# ProPrj__B__2024-11-30.net
KiCad netlist of a schematic drawn in EasyEDA Pro
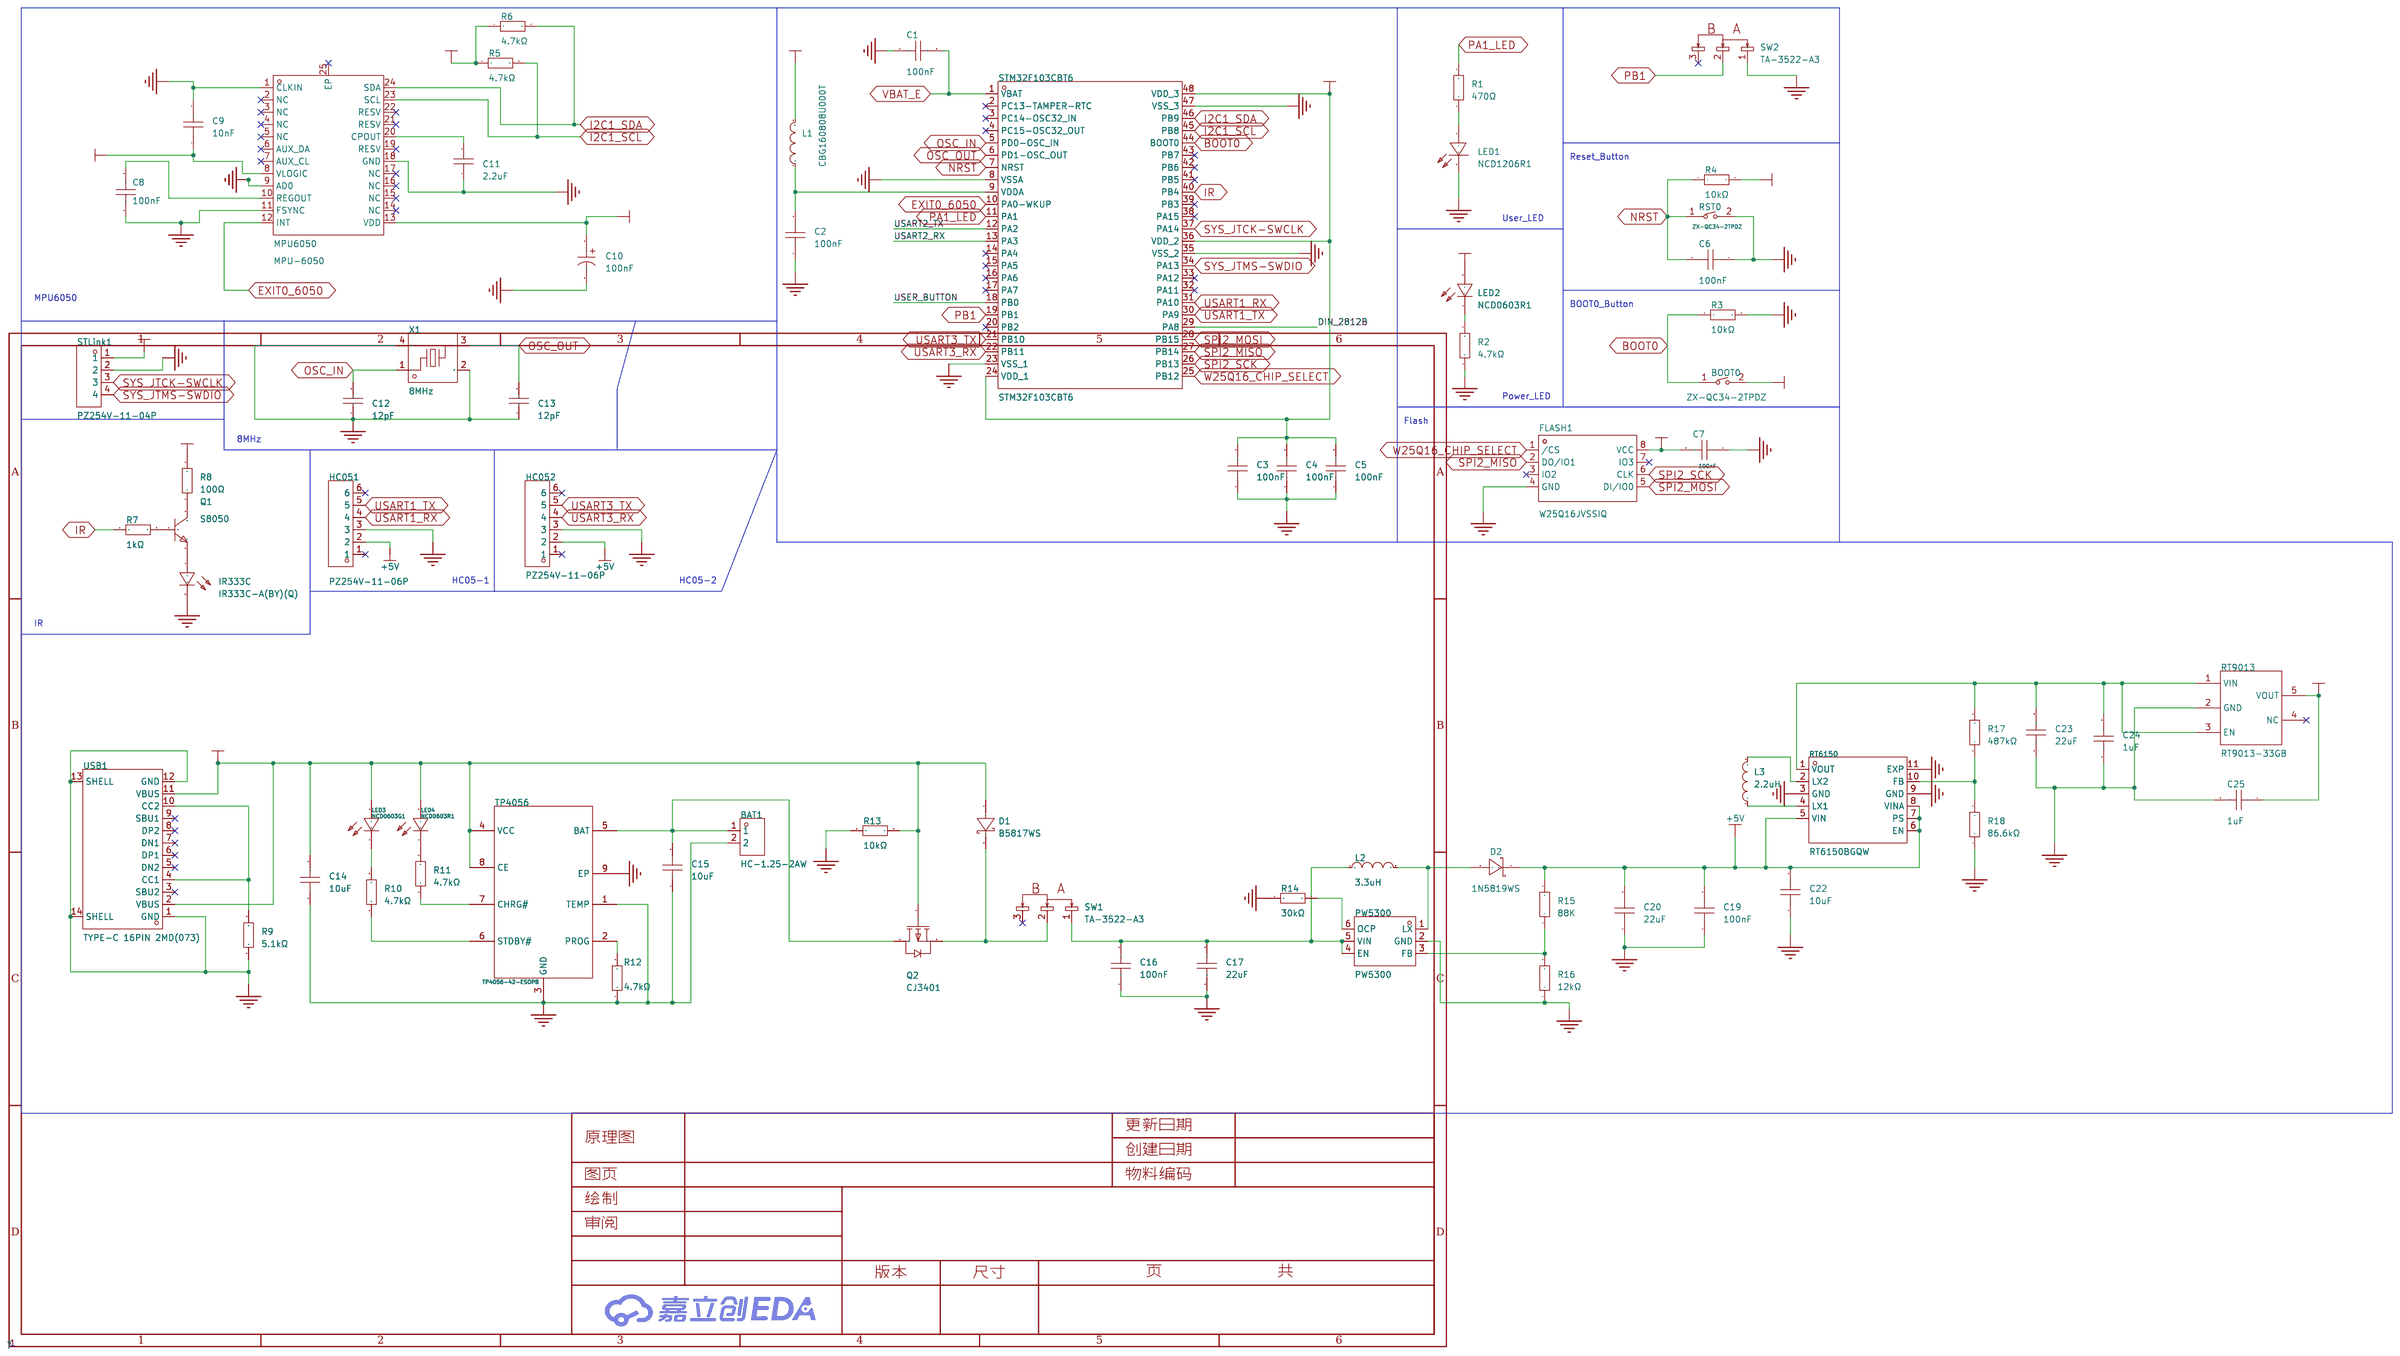
[diagram p0: schematic sheet]

(export (version "E")
  (design (tool "Eeschema 10.0.6"))
  (components
    (comp (ref "BAT1")
      (value "HC-1.25-2AW")
      (footprint "easyedapro:CONN-TH_2P-P1.25_HCTL_HC-1.25-2AW")
      (fields (field (name "Manufacturer") "HCTL(华灿天禄)"))
      (libsource (lib "easyedapro") (part "HC-1.25-2AW"))
    )
    (comp (ref "BOOT0")
      (value "ZX-QC34-2TPDZ")
      (footprint "easyedapro:KEY-SMD_L3.9-W3.0-LS5.0-EH")
      (fields (field (name "Manufacturer") "Megastar(兆星)"))
      (libsource (lib "easyedapro") (part "ZX-QC34-2TPDZ"))
    )
    (comp (ref "C1")
      (value "100nF")
      (footprint "easyedapro:C0603")
      (description "容值:100nF;精度:±10%;额定电压:50V;材质(温度系数):X7R;")
      (fields
        (field (name "Manufacturer Part") "CC0603KRX7R9BB104")
        (field (name "Manufacturer") "YAGEO(国巨)")
      )
      (libsource (lib "easyedapro") (part "CC0603KRX7R9BB104"))
    )
    (comp (ref "C2")
      (value "100nF")
      (footprint "easyedapro:C0603")
      (description "容值:100nF;精度:±10%;额定电压:50V;材质(温度系数):X7R;")
      (fields
        (field (name "Manufacturer Part") "CC0603KRX7R9BB104")
        (field (name "Manufacturer") "YAGEO(国巨)")
      )
      (libsource (lib "easyedapro") (part "CC0603KRX7R9BB104"))
    )
    (comp (ref "C3")
      (value "100nF")
      (footprint "easyedapro:C0603")
      (description "容值:100nF;精度:±10%;额定电压:50V;材质(温度系数):X7R;")
      (fields
        (field (name "Manufacturer Part") "CC0603KRX7R9BB104")
        (field (name "Manufacturer") "YAGEO(国巨)")
      )
      (libsource (lib "easyedapro") (part "CC0603KRX7R9BB104"))
    )
    (comp (ref "C4")
      (value "100nF")
      (footprint "easyedapro:C0603")
      (description "容值:100nF;精度:±10%;额定电压:50V;材质(温度系数):X7R;")
      (fields
        (field (name "Manufacturer Part") "CC0603KRX7R9BB104")
        (field (name "Manufacturer") "YAGEO(国巨)")
      )
      (libsource (lib "easyedapro") (part "CC0603KRX7R9BB104"))
    )
    (comp (ref "C5")
      (value "100nF")
      (footprint "easyedapro:C0603")
      (description "容值:100nF;精度:±10%;额定电压:50V;材质(温度系数):X7R;")
      (fields
        (field (name "Manufacturer Part") "CC0603KRX7R9BB104")
        (field (name "Manufacturer") "YAGEO(国巨)")
      )
      (libsource (lib "easyedapro") (part "CC0603KRX7R9BB104"))
    )
    (comp (ref "C6")
      (value "100nF")
      (footprint "easyedapro:C0603")
      (description "容值:100nF;精度:±10%;额定电压:50V;材质(温度系数):X7R;")
      (fields
        (field (name "Manufacturer Part") "CC0603KRX7R9BB104")
        (field (name "Manufacturer") "YAGEO(国巨)")
      )
      (libsource (lib "easyedapro") (part "CC0603KRX7R9BB104"))
    )
    (comp (ref "C7")
      (value "100nF")
      (footprint "easyedapro:C0603")
      (description "容值:100nF;精度:±10%;额定电压:50V;材质(温度系数):X7R;")
      (fields
        (field (name "Manufacturer Part") "CC0603KRX7R9BB104")
        (field (name "Manufacturer") "YAGEO(国巨)")
      )
      (libsource (lib "easyedapro") (part "CC0603KRX7R9BB104"))
    )
    (comp (ref "C8")
      (value "100nF")
      (footprint "easyedapro:C0603")
      (description "容值:100nF;精度:±10%;额定电压:50V;材质(温度系数):X7R;")
      (fields
        (field (name "Manufacturer Part") "CC0603KRX7R9BB104")
        (field (name "Manufacturer") "YAGEO(国巨)")
      )
      (libsource (lib "easyedapro") (part "CC0603KRX7R9BB104"))
    )
    (comp (ref "C9")
      (value "10nF")
      (footprint "easyedapro:C0603")
      (description "容值:100nF;精度:±10%;额定电压:50V;材质(温度系数):X7R;")
      (fields
        (field (name "Manufacturer Part") "CC0603KRX7R9BB103")
        (field (name "Manufacturer") "YAGEO(国巨)")
      )
      (libsource (lib "easyedapro") (part "CC0603KRX7R9BB104"))
    )
    (comp (ref "C10")
      (value "100nF")
      (footprint "easyedapro:CAP-SMD_L3.2-W1.6-FD")
      (description "容值:100nF;精度:±20%;额定电压:50V;等效串联电阻:20Ω;")
      (fields
        (field (name "Manufacturer Part") "CA45-A-35V-0.1UF-K")
        (field (name "Manufacturer") "CEC(振华新云)")
      )
      (libsource (lib "easyedapro") (part "T491A104M050AT"))
    )
    (comp (ref "C11")
      (value "2.2uF")
      (footprint "easyedapro:C0603")
      (description "容值:2.2uF;精度:±10%;额定电压:16V;材质(温度系数):X5R;")
      (fields
        (field (name "Manufacturer Part") "CL10A225KO8NNNC")
        (field (name "Manufacturer") "SAMSUNG(三星)")
      )
      (libsource (lib "easyedapro") (part "CL10A225KO8NNNC"))
    )
    (comp (ref "C12")
      (value "12pF")
      (footprint "easyedapro:C0603")
      (description "容值:12pF;精度:±5%;额定电压:50V;材质(温度系数):C0G;")
      (fields
        (field (name "Manufacturer Part") "CL10C120JB8NNNC")
        (field (name "Manufacturer") "SAMSUNG(三星)")
      )
      (libsource (lib "easyedapro") (part "CL10C120JB8NNNC"))
    )
    (comp (ref "C13")
      (value "12pF")
      (footprint "easyedapro:C0603")
      (description "容值:12pF;精度:±5%;额定电压:50V;材质(温度系数):C0G;")
      (fields
        (field (name "Manufacturer Part") "CL10C120JB8NNNC")
        (field (name "Manufacturer") "SAMSUNG(三星)")
      )
      (libsource (lib "easyedapro") (part "CL10C120JB8NNNC"))
    )
    (comp (ref "C14")
      (value "10uF")
      (footprint "easyedapro:C0603")
      (description "容值:10uF;精度:±20%;额定电压:16V;材质(温度系数):X5R;")
      (fields
        (field (name "Manufacturer Part") "HGC0603R5106M160NTHJ")
        (field (name "Manufacturer") "Chinocera(华瓷)")
      )
      (libsource (lib "easyedapro") (part "HGC0603R5106M160NTHJ"))
    )
    (comp (ref "C15")
      (value "10uF")
      (footprint "easyedapro:C0603")
      (description "容值:10uF;精度:±20%;额定电压:16V;材质(温度系数):X5R;")
      (fields
        (field (name "Manufacturer Part") "HGC0603R5106M160NTHJ")
        (field (name "Manufacturer") "Chinocera(华瓷)")
      )
      (libsource (lib "easyedapro") (part "HGC0603R5106M160NTHJ"))
    )
    (comp (ref "C16")
      (value "100nF")
      (footprint "easyedapro:C0603")
      (description "容值:100nF;精度:±10%;额定电压:50V;材质(温度系数):X7R;")
      (fields
        (field (name "Manufacturer Part") "CGA0603X7R104K500JT")
        (field (name "Manufacturer") "HRE(芯声)")
      )
      (libsource (lib "easyedapro") (part "cga0603x7r104k500jt"))
    )
    (comp (ref "C17")
      (value "22uF")
      (footprint "easyedapro:C0805")
      (description "容值:22uF;精度:±20%;额定电压:35V;材质(温度系数):X5R;")
      (fields
        (field (name "Manufacturer Part") "CGA0603X5R226M160JT")
        (field (name "Manufacturer") "HRE(芯声)")
      )
      (libsource (lib "easyedapro") (part "CGA0805X5R226M350MT"))
    )
    (comp (ref "C19")
      (value "100nF")
      (footprint "easyedapro:C0603")
      (description "容值:100nF;精度:±10%;额定电压:50V;材质(温度系数):X7R;")
      (fields
        (field (name "Manufacturer Part") "CGA0603X7R104K500JT")
        (field (name "Manufacturer") "HRE(芯声)")
      )
      (libsource (lib "easyedapro") (part "cga0603x7r104k500jt"))
    )
    (comp (ref "C20")
      (value "22uF")
      (footprint "easyedapro:C0805")
      (description "容值:22uF;精度:±20%;额定电压:35V;材质(温度系数):X5R;")
      (fields
        (field (name "Manufacturer Part") "CGA0603X5R226M160JT")
        (field (name "Manufacturer") "HRE(芯声)")
      )
      (libsource (lib "easyedapro") (part "CGA0805X5R226M350MT"))
    )
    (comp (ref "C22")
      (value "10uF")
      (footprint "easyedapro:C0603")
      (description "容值:10uF;精度:±20%;额定电压:16V;材质(温度系数):X5R;")
      (fields
        (field (name "Manufacturer Part") "HGC0603R5106M160NTHJ")
        (field (name "Manufacturer") "Chinocera(华瓷)")
      )
      (libsource (lib "easyedapro") (part "HGC0603R5106M160NTHJ"))
    )
    (comp (ref "C23")
      (value "22uF")
      (footprint "easyedapro:C0603")
      (description "容值:22uF;精度:±20%;额定电压:16V;材质(温度系数):X5R;")
      (fields
        (field (name "Manufacturer Part") "CGA0603X5R226M160JT")
        (field (name "Manufacturer") "HRE(芯声)")
      )
      (libsource (lib "easyedapro") (part "CGA0603X5R226M160JT"))
    )
    (comp (ref "C24")
      (value "1uF")
      (footprint "easyedapro:C0603")
      (description "容值:1uF;精度:±10%;额定电压:16V;材质(温度系数):X5R;")
      (fields
        (field (name "Manufacturer Part") "CGA0603X5R105K160JT")
        (field (name "Manufacturer") "HRE(芯声)")
      )
      (libsource (lib "easyedapro") (part "CGA0603X5R105K160JT"))
    )
    (comp (ref "C25")
      (value "1uF")
      (footprint "easyedapro:C0603")
      (description "容值:1uF;精度:±10%;额定电压:16V;材质(温度系数):X5R;")
      (fields
        (field (name "Manufacturer Part") "CGA0603X5R105K160JT")
        (field (name "Manufacturer") "HRE(芯声)")
      )
      (libsource (lib "easyedapro") (part "CGA0603X5R105K160JT"))
    )
    (comp (ref "D1")
      (value "B5817WS")
      (footprint "easyedapro:SOD-323_L1.7-W1.3-LS2.5-FD")
      (description "二极管配置:独立式;正向压降(Vf):450mV@1.0A;直流反向耐压(Vr):20V;平均整流电流(Io):1A;")
      (fields (field (name "Manufacturer") "宏迦橙"))
      (libsource (lib "easyedapro") (part "B5817WS_C7420329"))
    )
    (comp (ref "D2")
      (value "1N5819WS")
      (footprint "easyedapro:SMB_L4.6-W3.6-LS5.3-RD")
      (description "正向压降(Vf):500mV@3A;直流反向耐压(Vr):40V;平均整流电流(Io):3A;")
      (fields (field (name "Manufacturer") "Hottech(合科泰)"))
      (libsource (lib "easyedapro") (part "SS34_C266556"))
    )
    (comp (ref "FLASH1")
      (value "W25Q16JVSSIQ")
      (footprint "easyedapro:SOIC-8_L5.3-W5.3-P1.27-LS8.0-BL")
      (description "（与C82317为同一颗物料，只是编带方式不一样。）3V 16Mbit Serial Flash Memory with dual/quad SPI")
      (fields (field (name "Manufacturer") "WINBOND(华邦)"))
      (libsource (lib "easyedapro") (part "W25Q16JVSSIQTR"))
    )
    (comp (ref "HC051")
      (value "PZ254V-11-06P")
      (footprint "easyedapro:HDR-TH_6P-P2.54-V-M")
      (fields (field (name "Manufacturer") "XFCN(兴飞)"))
      (libsource (lib "easyedapro") (part "PZ254V-11-06P"))
    )
    (comp (ref "HC052")
      (value "PZ254V-11-06P")
      (footprint "easyedapro:HDR-TH_6P-P2.54-V-M")
      (fields (field (name "Manufacturer") "XFCN(兴飞)"))
      (libsource (lib "easyedapro") (part "PZ254V-11-06P"))
    )
    (comp (ref "IR333C")
      (value "IR333C-A(BY)(Q)")
      (footprint "easyedapro:LED-TH_BD5.0-P2.54-FD")
      (description "波长:940nm;")
      (fields (field (name "Manufacturer") "EVERLIGHT(亿光)"))
      (libsource (lib "easyedapro") (part "ir333c-a(by)(q)"))
    )
    (comp (ref "L1")
      (value "CBG160808U000T")
      (footprint "easyedapro:L0603")
      (description "标称阻抗@测试频率:0Ω@100MHz;直流电阻(RDC):100mΩ;")
      (fields (field (name "Manufacturer") "FH(风华)"))
      (libsource (lib "easyedapro") (part "CBG160808U000T"))
    )
    (comp (ref "L2")
      (value "3.3uH")
      (footprint "easyedapro:IND-SMD_L5.4-W5.2_FXL0530")
      (description "电感值:4.7uH;精度:±20%;额定电流:4.5A;饱和电流(Isat):5A;类型:一体成型电感;")
      (fields (field (name "Manufacturer Part") "VLS252012CX-3R3M-1") (field (name "Manufacturer") "TDK"))
      (libsource (lib "easyedapro") (part "FXL0530-4R7-M"))
    )
    (comp (ref "L3")
      (value "2.2uH")
      (footprint "easyedapro:IND-SMD_L2.5-W2.0_MHCHL2520")
      (description "电感值:2.2uH;精度:±20%;额定电流:3A;饱和电流(Isat):3.8A;类型:一体成型电感;")
      (fields
        (field (name "Manufacturer Part") "FTC252012S2R2MBCA")
        (field (name "Manufacturer") "cjiang(长江微电)")
      )
      (libsource (lib "easyedapro") (part "FTC252012S2R2MBCA"))
    )
    (comp (ref "LED1")
      (value "NCD1206R1")
      (footprint "easyedapro:LED1206-R-RD_RED")
      (fields (field (name "Manufacturer") "国星光电"))
      (libsource (lib "easyedapro") (part "FC-3215HRK-620D"))
    )
    (comp (ref "LED2")
      (value "NCD0603R1")
      (footprint "easyedapro:LED0603-RD_RED")
      (fields (field (name "Manufacturer") "国星光电"))
      (libsource (lib "easyedapro") (part "FC-DA1608HRK-620D"))
    )
    (comp (ref "LED3")
      (value "NCD0603G1")
      (footprint "easyedapro:led0603-rd_1")
      (fields (field (name "Manufacturer") "国星光电"))
      (libsource (lib "easyedapro") (part "FC-D1608UGK-520D10"))
    )
    (comp (ref "LED4")
      (value "NCD0603R1")
      (footprint "easyedapro:led0603-rd_1")
      (fields (field (name "Manufacturer") "国星光电"))
      (libsource (lib "easyedapro") (part "FC-D1608UGK-520D10"))
    )
    (comp (ref "MPU6050")
      (value "MPU-6050")
      (footprint "easyedapro:QFN-24_L4.0-W4.0-P0.50-BL-EP2.7")
      (description "传感器类型:加速度计陀螺仪;")
      (fields (field (name "Manufacturer") "TDK InvenSense(应美盛)"))
      (libsource (lib "easyedapro") (part "MPU-6050_C24112"))
    )
    (comp (ref "PW5300")
      (value "PW5300")
      (footprint "easyedapro:SOT-23-6_L2.9-W1.6-P0.95-LS2.8-BL")
      (libsource (lib "easyedapro") (part "PW5300"))
    )
    (comp (ref "Q1")
      (value "S8050")
      (footprint "easyedapro:SOT-23-3_L2.9-W1.6-P1.90-LS2.8-BR")
      (description "晶体管类型:NPN;集电极电流(Ic):500mA;集射极击穿电压(Vceo):25V;功率(Pd):300mW;")
      (fields (field (name "Manufacturer") "Hottech(合科泰)"))
      (libsource (lib "easyedapro") (part "S8050_C181158"))
    )
    (comp (ref "Q2")
      (value "CJ3401")
      (footprint "easyedapro:SOT-23-3_L2.9-W1.6-P1.90-LS2.8-BR")
      (fields (field (name "Manufacturer") "CJ(江苏长电/长晶)"))
      (libsource (lib "easyedapro") (part "CJ3401"))
    )
    (comp (ref "R1")
      (value "470Ω")
      (footprint "easyedapro:R0603")
      (description "电阻类型:厚膜电阻;阻值:470Ω;精度:±1%;功率:100mW;最大工作电压:75V;温度系数:±100ppm/°C;")
      (fields
        (field (name "Manufacturer Part") "0603WAF4700T5E")
        (field (name "Manufacturer") "UNI-ROYAL(厚声)")
      )
      (libsource (lib "easyedapro") (part "0603WAF4700T5E"))
    )
    (comp (ref "R2")
      (value "4.7kΩ")
      (footprint "easyedapro:R0603")
      (description "电阻类型:厚膜电阻;阻值:4.7kΩ;精度:±1%;功率:100mW;最大工作电压:75V;温度系数:±100ppm/°C;")
      (fields
        (field (name "Manufacturer Part") "0603WAF4701T5E")
        (field (name "Manufacturer") "UNI-ROYAL(厚声)")
      )
      (libsource (lib "easyedapro") (part "0603WAF4701T5E"))
    )
    (comp (ref "R3")
      (value "10kΩ")
      (footprint "easyedapro:R0603")
      (description "电阻类型:厚膜电阻;阻值:10kΩ;精度:±1%;功率:100mW;最大工作电压:75V;温度系数:±100ppm/°C;")
      (fields
        (field (name "Manufacturer Part") "0603WAF1002T5E")
        (field (name "Manufacturer") "UNI-ROYAL(厚声)")
      )
      (libsource (lib "easyedapro") (part "0603WAF1002T5E"))
    )
    (comp (ref "R4")
      (value "10kΩ")
      (footprint "easyedapro:R0603")
      (description "电阻类型:厚膜电阻;阻值:10kΩ;精度:±1%;功率:100mW;最大工作电压:75V;温度系数:±100ppm/°C;")
      (fields
        (field (name "Manufacturer Part") "0603WAF1002T5E")
        (field (name "Manufacturer") "UNI-ROYAL(厚声)")
      )
      (libsource (lib "easyedapro") (part "0603WAF1002T5E"))
    )
    (comp (ref "R5")
      (value "4.7kΩ")
      (footprint "easyedapro:R0603")
      (description "电阻类型:厚膜电阻;阻值:4.7kΩ;精度:±1%;功率:100mW;最大工作电压:75V;温度系数:±100ppm/°C;")
      (fields
        (field (name "Manufacturer Part") "0603WAF4701T5E")
        (field (name "Manufacturer") "UNI-ROYAL(厚声)")
      )
      (libsource (lib "easyedapro") (part "0603WAF4701T5E"))
    )
    (comp (ref "R6")
      (value "4.7kΩ")
      (footprint "easyedapro:R0603")
      (description "电阻类型:厚膜电阻;阻值:4.7kΩ;精度:±1%;功率:100mW;最大工作电压:75V;温度系数:±100ppm/°C;")
      (fields
        (field (name "Manufacturer Part") "0603WAF4701T5E")
        (field (name "Manufacturer") "UNI-ROYAL(厚声)")
      )
      (libsource (lib "easyedapro") (part "0603WAF4701T5E"))
    )
    (comp (ref "R7")
      (value "1kΩ")
      (footprint "easyedapro:R0603")
      (description "电阻类型:厚膜电阻;阻值:1kΩ;精度:±1%;功率:100mW;最大工作电压:75V;温度系数:±100ppm/°C;")
      (fields
        (field (name "Manufacturer Part") "0603WAF1001T5E")
        (field (name "Manufacturer") "UNI-ROYAL(厚声)")
      )
      (libsource (lib "easyedapro") (part "0603WAF1001T5E"))
    )
    (comp (ref "R8")
      (value "100Ω")
      (footprint "easyedapro:R0603")
      (description "电阻类型:厚膜电阻;阻值:100Ω;精度:±1%;功率:100mW;最大工作电压:75V;温度系数:±200ppm/°C;")
      (fields
        (field (name "Manufacturer Part") "0603WAF1000T5E")
        (field (name "Manufacturer") "UNI-ROYAL(厚声)")
      )
      (libsource (lib "easyedapro") (part "0603WAF1000T5E"))
    )
    (comp (ref "R9")
      (value "5.1kΩ")
      (footprint "easyedapro:R0603")
      (description "电阻类型:厚膜电阻;阻值:5.1kΩ;精度:±1%;功率:100mW;最大工作电压:75V;温度系数:±100ppm/°C;")
      (fields
        (field (name "Manufacturer Part") "0603WAF5101T5E")
        (field (name "Manufacturer") "UNI-ROYAL(厚声)")
      )
      (libsource (lib "easyedapro") (part "0603WAF5101T5E"))
    )
    (comp (ref "R10")
      (value "4.7kΩ")
      (footprint "easyedapro:R0603")
      (description "电阻类型:厚膜电阻;阻值:4.7kΩ;精度:±1%;功率:100mW;最大工作电压:75V;温度系数:±100ppm/°C;")
      (fields
        (field (name "Manufacturer Part") "0603WAF4701T5E")
        (field (name "Manufacturer") "UNI-ROYAL(厚声)")
      )
      (libsource (lib "easyedapro") (part "0603WAF4701T5E"))
    )
    (comp (ref "R11")
      (value "4.7kΩ")
      (footprint "easyedapro:R0603")
      (description "电阻类型:厚膜电阻;阻值:4.7kΩ;精度:±1%;功率:100mW;最大工作电压:75V;温度系数:±100ppm/°C;")
      (fields
        (field (name "Manufacturer Part") "0603WAF4701T5E")
        (field (name "Manufacturer") "UNI-ROYAL(厚声)")
      )
      (libsource (lib "easyedapro") (part "0603WAF4701T5E"))
    )
    (comp (ref "R12")
      (value "4.7kΩ")
      (footprint "easyedapro:R0603")
      (description "电阻类型:厚膜电阻;阻值:4.7kΩ;精度:±1%;功率:100mW;最大工作电压:75V;温度系数:±100ppm/°C;")
      (fields
        (field (name "Manufacturer Part") "0603WAF4701T5E")
        (field (name "Manufacturer") "UNI-ROYAL(厚声)")
      )
      (libsource (lib "easyedapro") (part "0603WAF4701T5E"))
    )
    (comp (ref "R13")
      (value "10kΩ")
      (footprint "easyedapro:R0603")
      (description "电阻类型:厚膜电阻;阻值:10kΩ;精度:±1%;功率:100mW;最大工作电压:75V;温度系数:±100ppm/°C;")
      (fields
        (field (name "Manufacturer Part") "0603WAF1002T5E")
        (field (name "Manufacturer") "UNI-ROYAL(厚声)")
      )
      (libsource (lib "easyedapro") (part "0603WAF1002T5E"))
    )
    (comp (ref "R14")
      (value "30kΩ")
      (footprint "easyedapro:R0603")
      (description "电阻类型:厚膜电阻;阻值:30kΩ;精度:±1%;功率:100mW;最大工作电压:75V;温度系数:±100ppm/°C;")
      (fields
        (field (name "Manufacturer Part") "0603WAF3002T5E")
        (field (name "Manufacturer") "UNI-ROYAL(厚声)")
      )
      (libsource (lib "easyedapro") (part "0603WAF3002T5E"))
    )
    (comp (ref "R15")
      (value "88K")
      (footprint "easyedapro:R0603")
      (fields
        (field (name "Manufacturer Part") "RCT0388K7FLF")
        (field (name "Manufacturer") "HKR(香港电阻)")
        (field (name "Tolerance") "±1%")
      )
      (libsource (lib "easyedapro") (part "电阻"))
    )
    (comp (ref "R16")
      (value "12kΩ")
      (footprint "easyedapro:R0603")
      (description "电阻类型:厚膜电阻;阻值:12kΩ;精度:±1%;功率:100mW;最大工作电压:75V;温度系数:±100ppm/°C;")
      (fields
        (field (name "Manufacturer Part") "0603WAF1202T5E")
        (field (name "Manufacturer") "UNI-ROYAL(厚声)")
      )
      (libsource (lib "easyedapro") (part "0603WAF1202T5E"))
    )
    (comp (ref "R17")
      (value "487kΩ")
      (footprint "easyedapro:R0603")
      (description "电阻类型:厚膜电阻;阻值:487kΩ;精度:±1%;功率:100mW;最大工作电压:75V;温度系数:±100ppm/°C;")
      (fields
        (field (name "Manufacturer Part") "0603WAF4873T5E")
        (field (name "Manufacturer") "UNI-ROYAL(厚声)")
      )
      (libsource (lib "easyedapro") (part "0603WAF4873T5E"))
    )
    (comp (ref "R18")
      (value "86.6kΩ")
      (footprint "easyedapro:R0603")
      (description "电阻类型:厚膜电阻;阻值:86.6kΩ;精度:±1%;功率:100mW;最大工作电压:75V;温度系数:±100ppm/°C;")
      (fields
        (field (name "Manufacturer Part") "0603WAF8662T5E")
        (field (name "Manufacturer") "UNI-ROYAL(厚声)")
      )
      (libsource (lib "easyedapro") (part "0603WAF8662T5E"))
    )
    (comp (ref "RST0")
      (value "ZX-QC34-2TPDZ")
      (footprint "easyedapro:KEY-SMD_L3.9-W3.0-LS5.0-EH")
      (fields (field (name "Manufacturer") "Megastar(兆星)"))
      (libsource (lib "easyedapro") (part "ZX-QC34-2TPDZ"))
    )
    (comp (ref "RT6150")
      (value "RT6150BGQW")
      (footprint "easyedapro:WSON-10_L2.5-W2.5-P0.50-BL-EP")
      (description "功能类型:升降压型;输入电压:1.8V~5.5V;输出电压:1.8V~5.5V;输出电流(最大值):800mA;")
      (fields (field (name "Manufacturer") "RICHTEK(立锜)"))
      (libsource (lib "easyedapro") (part "RT6150BGQW"))
    )
    (comp (ref "RT9013")
      (value "RT9013-33GB")
      (footprint "easyedapro:SOT-23-5_L3.0-W1.7-P0.95-LS2.8-BL")
      (description "输出类型:固定;最大输入电压:5.5V;输出电压:3.3V;最大输出电流:500mA;电源纹波抑制比(PSRR):50dB@(10kHz);输出极性:正极;")
      (fields (field (name "Manufacturer") "RICHTEK(立锜)"))
      (libsource (lib "easyedapro") (part "RT9013-33GB"))
    )
    (comp (ref "STLink1")
      (value "PZ254V-11-04P")
      (footprint "easyedapro:HDR-TH_4P-P2.54-V-M")
      (fields (field (name "Manufacturer") "XFCN(兴飞)"))
      (libsource (lib "easyedapro") (part "PZ254V-11-04P_C2691448"))
    )
    (comp (ref "STM32F103CBT6")
      (value "STM32F103CBT6")
      (fields (field (name "Manufacturer") "ST(意法半导体)"))
      (libsource (lib "easyedapro") (part "APM32F103CBT6"))
    )
    (comp (ref "SW1")
      (value "TA-3522-A3")
      (footprint "easyedapro:SW-TH_3P-L9.1-W3.5-P2.50-A3")
      (fields (field (name "Manufacturer") "Yuandi(元迪)"))
      (libsource (lib "easyedapro") (part "TA-3522-A3"))
    )
    (comp (ref "SW2")
      (value "TA-3522-A3")
      (footprint "easyedapro:SW-TH_3P-L9.1-W3.5-P2.50-A3")
      (fields (field (name "Manufacturer") "Yuandi(元迪)"))
      (libsource (lib "easyedapro") (part "TA-3522-A3"))
    )
    (comp (ref "TP4056")
      (value "TP4056-42-ESOP8")
      (footprint "easyedapro:ESOP-8_L4.9-W3.9-P1.27-LS6.0-BL-EP")
      (description "锂电池充电芯片 42代表电池满电电压4.2V。")
      (fields (field (name "Manufacturer") "TOPPOWER(南京拓微)"))
      (libsource (lib "easyedapro") (part "TP4056"))
    )
    (comp (ref "USB1")
      (value "TYPE-C 16PIN 2MD(073)")
      (footprint "easyedapro:USB-C-SMD_TYPE-C-6PIN-2MD-073")
      (description "连接器类型:Type-C;标准:USB 3.1;公母:母;安装方式:卧贴;触点数量:16P;端口数量:1;额定电流 - 电源:5A;工作温度范围:-25°C~+85°C;")
      (fields (field (name "Manufacturer") "SHOU HAN(首韩)"))
      (libsource (lib "easyedapro") (part "TYPE-C 16PIN 2MD(073)"))
    )
    (comp (ref "X1")
      (value "8MHz")
      (footprint "easyedapro:OSC-SMD_4P-L3.2-W2.5-BL")
      (description "晶振类型:贴片晶振;频率:8MHz;常温频差:±10ppm;外接负载电容:12pF;频率稳定度(全温):±20ppm;")
      (fields (field (name "Manufacturer Part") "X32258MOB4SI") (field (name "Manufacturer") "YXC(扬兴晶振)"))
      (libsource (lib "easyedapro") (part "x32258mob4si"))
    )
  )
  (nets
    (net (code "1") (name "+5V") (class "Default")
      (node (ref "C19") (pin "2") (pinfunction "2_2") (pintype "unspecified"))
      (node (ref "C20") (pin "2") (pinfunction "2_2") (pintype "unspecified"))
      (node (ref "C22") (pin "2") (pinfunction "2_2") (pintype "unspecified"))
      (node (ref "D2") (pin "1") (pinfunction "C_1") (pintype "unspecified"))
      (node (ref "HC051") (pin "2") (pinfunction "2_2") (pintype "unspecified"))
      (node (ref "HC052") (pin "2") (pinfunction "2_2") (pintype "unspecified"))
      (node (ref "R15") (pin "2") (pinfunction "2_2") (pintype "input"))
      (node (ref "RT6150") (pin "5") (pinfunction "VIN_5") (pintype "input"))
      (node (ref "RT6150") (pin "6") (pinfunction "EN_6") (pintype "input"))
      (node (ref "RT6150") (pin "7") (pinfunction "PS_7") (pintype "input"))
      (node (ref "RT6150") (pin "8") (pinfunction "VINA_8") (pintype "input"))
    )
    (net (code "2") (name "/DIN_2812B") (class "Default")
      (node (ref "STM32F103CBT6") (pin "29") (pinfunction "PA8_29") (pintype "unspecified"))
    )
    (net (code "3") (name "/USART2_RX") (class "Default")
      (node (ref "STM32F103CBT6") (pin "13") (pinfunction "PA3_13") (pintype "unspecified"))
    )
    (net (code "4") (name "/USART2_TX") (class "Default")
      (node (ref "STM32F103CBT6") (pin "12") (pinfunction "PA2_12") (pintype "unspecified"))
    )
    (net (code "5") (name "/USER_BUTTON") (class "Default")
      (node (ref "STM32F103CBT6") (pin "18") (pinfunction "PB0_18") (pintype "unspecified"))
    )
    (net (code "6") (name "3V3") (class "Default")
      (node (ref "BOOT0") (pin "2") (pinfunction "2_2") (pintype "unspecified"))
      (node (ref "C10") (pin "1") (pinfunction "1_1") (pintype "input"))
      (node (ref "C25") (pin "1") (pinfunction "1_1") (pintype "unspecified"))
      (node (ref "C3") (pin "2") (pinfunction "2_2") (pintype "unspecified"))
      (node (ref "C4") (pin "2") (pinfunction "2_2") (pintype "unspecified"))
      (node (ref "C5") (pin "2") (pinfunction "2_2") (pintype "unspecified"))
      (node (ref "C7") (pin "2") (pinfunction "2_2") (pintype "unspecified"))
      (node (ref "C9") (pin "1") (pinfunction "1_1") (pintype "unspecified"))
      (node (ref "FLASH1") (pin "8") (pinfunction "VCC_8") (pintype "unspecified"))
      (node (ref "L1") (pin "2") (pinfunction "2_2") (pintype "unspecified"))
      (node (ref "LED2") (pin "2") (pinfunction "A_2") (pintype "input"))
      (node (ref "MPU6050") (pin "13") (pinfunction "VDD_13") (pintype "unspecified"))
      (node (ref "MPU6050") (pin "8") (pinfunction "VLOGIC_8") (pintype "unspecified"))
      (node (ref "R4") (pin "2") (pinfunction "2_2") (pintype "input"))
      (node (ref "R5") (pin "1") (pinfunction "1_1") (pintype "input"))
      (node (ref "R6") (pin "1") (pinfunction "1_1") (pintype "input"))
      (node (ref "R8") (pin "2") (pinfunction "2_2") (pintype "input"))
      (node (ref "RT9013") (pin "5") (pinfunction "VOUT_5") (pintype "unspecified"))
      (node (ref "STLink1") (pin "1") (pinfunction "1_1") (pintype "unspecified"))
      (node (ref "STM32F103CBT6") (pin "24") (pinfunction "VDD_1_24") (pintype "unspecified"))
      (node (ref "STM32F103CBT6") (pin "36") (pinfunction "VDD_2_36") (pintype "unspecified"))
      (node (ref "STM32F103CBT6") (pin "48") (pinfunction "VDD_3_48") (pintype "unspecified"))
    )
    (net (code "7") (name "BOOT0") (class "Default")
      (node (ref "BOOT0") (pin "1") (pinfunction "1_1") (pintype "unspecified"))
      (node (ref "R3") (pin "1") (pinfunction "1_1") (pintype "input"))
      (node (ref "STM32F103CBT6") (pin "44") (pinfunction "BOOT0_44") (pintype "unspecified"))
    )
    (net (code "8") (name "EXIT0_6050") (class "Default")
      (node (ref "MPU6050") (pin "12") (pinfunction "INT_12") (pintype "unspecified"))
      (node (ref "STM32F103CBT6") (pin "10") (pinfunction "PA0-WKUP_10") (pintype "unspecified"))
    )
    (net (code "9") (name "GND") (class "Default")
      (node (ref "BAT1") (pin "2") (pinfunction "2_2") (pintype "unspecified"))
      (node (ref "C1") (pin "1") (pinfunction "1_1") (pintype "unspecified"))
      (node (ref "C10") (pin "2") (pinfunction "2_2") (pintype "input"))
      (node (ref "C11") (pin "1") (pinfunction "1_1") (pintype "input"))
      (node (ref "C12") (pin "1") (pinfunction "1_1") (pintype "input"))
      (node (ref "C13") (pin "1") (pinfunction "1_1") (pintype "input"))
      (node (ref "C14") (pin "1") (pinfunction "1_1") (pintype "unspecified"))
      (node (ref "C15") (pin "1") (pinfunction "1_1") (pintype "unspecified"))
      (node (ref "C16") (pin "1") (pinfunction "1_1") (pintype "unspecified"))
      (node (ref "C17") (pin "1") (pinfunction "1_1") (pintype "unspecified"))
      (node (ref "C19") (pin "1") (pinfunction "1_1") (pintype "unspecified"))
      (node (ref "C2") (pin "1") (pinfunction "1_1") (pintype "unspecified"))
      (node (ref "C20") (pin "1") (pinfunction "1_1") (pintype "unspecified"))
      (node (ref "C22") (pin "1") (pinfunction "1_1") (pintype "unspecified"))
      (node (ref "C23") (pin "1") (pinfunction "1_1") (pintype "unspecified"))
      (node (ref "C24") (pin "1") (pinfunction "1_1") (pintype "unspecified"))
      (node (ref "C25") (pin "2") (pinfunction "2_2") (pintype "unspecified"))
      (node (ref "C3") (pin "1") (pinfunction "1_1") (pintype "unspecified"))
      (node (ref "C4") (pin "1") (pinfunction "1_1") (pintype "unspecified"))
      (node (ref "C5") (pin "1") (pinfunction "1_1") (pintype "unspecified"))
      (node (ref "C6") (pin "1") (pinfunction "1_1") (pintype "unspecified"))
      (node (ref "C7") (pin "1") (pinfunction "1_1") (pintype "unspecified"))
      (node (ref "C8") (pin "1") (pinfunction "1_1") (pintype "unspecified"))
      (node (ref "C9") (pin "2") (pinfunction "2_2") (pintype "unspecified"))
      (node (ref "FLASH1") (pin "4") (pinfunction "GND_4") (pintype "unspecified"))
      (node (ref "HC051") (pin "3") (pinfunction "3_3") (pintype "unspecified"))
      (node (ref "HC052") (pin "3") (pinfunction "3_3") (pintype "unspecified"))
      (node (ref "IR333C") (pin "2") (pinfunction "C_2") (pintype "input"))
      (node (ref "LED1") (pin "2") (pinfunction "K_2") (pintype "unspecified"))
      (node (ref "MPU6050") (pin "1") (pinfunction "CLKIN_1") (pintype "unspecified"))
      (node (ref "MPU6050") (pin "11") (pinfunction "FSYNC_11") (pintype "unspecified"))
      (node (ref "MPU6050") (pin "18") (pinfunction "GND_18") (pintype "unspecified"))
      (node (ref "MPU6050") (pin "9") (pinfunction "AD0_9") (pintype "unspecified"))
      (node (ref "PW5300") (pin "2") (pinfunction "GND_2") (pintype "unspecified"))
      (node (ref "R12") (pin "1") (pinfunction "1_1") (pintype "input"))
      (node (ref "R13") (pin "1") (pinfunction "1_1") (pintype "input"))
      (node (ref "R14") (pin "1") (pinfunction "1_1") (pintype "input"))
      (node (ref "R16") (pin "1") (pinfunction "1_1") (pintype "input"))
      (node (ref "R18") (pin "1") (pinfunction "1_1") (pintype "input"))
      (node (ref "R2") (pin "1") (pinfunction "1_1") (pintype "input"))
      (node (ref "R3") (pin "2") (pinfunction "2_2") (pintype "input"))
      (node (ref "R9") (pin "1") (pinfunction "1_1") (pintype "input"))
      (node (ref "RST0") (pin "2") (pinfunction "2_2") (pintype "unspecified"))
      (node (ref "RT6150") (pin "11") (pinfunction "EXP_11") (pintype "input"))
      (node (ref "RT6150") (pin "3") (pinfunction "GND_3") (pintype "input"))
      (node (ref "RT6150") (pin "9") (pinfunction "GND_9") (pintype "input"))
      (node (ref "RT9013") (pin "2") (pinfunction "GND_2") (pintype "unspecified"))
      (node (ref "STLink1") (pin "2") (pinfunction "2_2") (pintype "unspecified"))
      (node (ref "STM32F103CBT6") (pin "23") (pinfunction "VSS_1_23") (pintype "unspecified"))
      (node (ref "STM32F103CBT6") (pin "35") (pinfunction "VSS_2_35") (pintype "unspecified"))
      (node (ref "STM32F103CBT6") (pin "47") (pinfunction "VSS_3_47") (pintype "unspecified"))
      (node (ref "STM32F103CBT6") (pin "8") (pinfunction "VSSA_8") (pintype "unspecified"))
      (node (ref "SW2") (pin "1") (pinfunction "1_1") (pintype "unspecified"))
      (node (ref "TP4056") (pin "1") (pinfunction "TEMP_1") (pintype "unspecified"))
      (node (ref "TP4056") (pin "3") (pinfunction "GND_3") (pintype "unspecified"))
      (node (ref "TP4056") (pin "9") (pinfunction "EP_9") (pintype "unspecified"))
      (node (ref "USB1") (pin "1") (pinfunction "GND_1") (pintype "unspecified"))
      (node (ref "USB1") (pin "12") (pinfunction "GND_12") (pintype "unspecified"))
      (node (ref "USB1") (pin "13") (pinfunction "SHELL_13") (pintype "unspecified"))
      (node (ref "USB1") (pin "14") (pinfunction "SHELL_14") (pintype "unspecified"))
      (node (ref "X1") (pin "2") (pinfunction "GND_2") (pintype "input"))
      (node (ref "X1") (pin "4") (pinfunction "GND_4") (pintype "input"))
    )
    (net (code "10") (name "I2C1_SCL") (class "Default")
      (node (ref "MPU6050") (pin "23") (pinfunction "SCL_23") (pintype "unspecified"))
      (node (ref "R5") (pin "2") (pinfunction "2_2") (pintype "input"))
      (node (ref "STM32F103CBT6") (pin "45") (pinfunction "PB8_45") (pintype "unspecified"))
    )
    (net (code "11") (name "I2C1_SDA") (class "Default")
      (node (ref "MPU6050") (pin "24") (pinfunction "SDA_24") (pintype "unspecified"))
      (node (ref "R6") (pin "2") (pinfunction "2_2") (pintype "input"))
      (node (ref "STM32F103CBT6") (pin "46") (pinfunction "PB9_46") (pintype "unspecified"))
    )
    (net (code "12") (name "IR") (class "Default")
      (node (ref "R7") (pin "1") (pinfunction "1_1") (pintype "input"))
      (node (ref "STM32F103CBT6") (pin "40") (pinfunction "PB4_40") (pintype "unspecified"))
    )
    (net (code "13") (name "NRST") (class "Default")
      (node (ref "C6") (pin "2") (pinfunction "2_2") (pintype "unspecified"))
      (node (ref "R4") (pin "1") (pinfunction "1_1") (pintype "input"))
      (node (ref "RST0") (pin "1") (pinfunction "1_1") (pintype "unspecified"))
      (node (ref "STM32F103CBT6") (pin "7") (pinfunction "NRST_7") (pintype "unspecified"))
    )
    (net (code "14") (name "Net-(D1-K)") (class "Default")
      (node (ref "D1") (pin "2") (pinfunction "K_2") (pintype "unspecified"))
      (node (ref "Q2") (pin "2") (pinfunction "S_2") (pintype "unspecified"))
      (node (ref "SW1") (pin "2") (pinfunction "2_2") (pintype "unspecified"))
    )
    (net (code "15") (name "Net-(D2-A)") (class "Default")
      (node (ref "D2") (pin "2") (pinfunction "A_2") (pintype "unspecified"))
      (node (ref "L2") (pin "2") (pinfunction "2_2") (pintype "unspecified"))
      (node (ref "PW5300") (pin "1") (pinfunction "LX_1") (pintype "unspecified"))
    )
    (net (code "16") (name "Net-(IR333C-A)") (class "Default")
      (node (ref "IR333C") (pin "1") (pinfunction "A_1") (pintype "input"))
      (node (ref "Q1") (pin "2") (pinfunction "2_2") (pintype "input"))
    )
    (net (code "17") (name "Net-(LED1-A)") (class "Default")
      (node (ref "LED1") (pin "1") (pinfunction "A_1") (pintype "unspecified"))
      (node (ref "R1") (pin "1") (pinfunction "1_1") (pintype "input"))
    )
    (net (code "18") (name "Net-(LED2-K)") (class "Default")
      (node (ref "LED2") (pin "1") (pinfunction "K_1") (pintype "input"))
      (node (ref "R2") (pin "2") (pinfunction "2_2") (pintype "input"))
    )
    (net (code "19") (name "Net-(LED3-K)") (class "Default")
      (node (ref "LED3") (pin "1") (pinfunction "K_1") (pintype "input"))
      (node (ref "R10") (pin "2") (pinfunction "2_2") (pintype "input"))
    )
    (net (code "20") (name "Net-(LED4-K)") (class "Default")
      (node (ref "LED4") (pin "1") (pinfunction "K_1") (pintype "input"))
      (node (ref "R11") (pin "2") (pinfunction "2_2") (pintype "input"))
    )
    (net (code "21") (name "Net-(MPU6050-CPOUT)") (class "Default")
      (node (ref "C11") (pin "2") (pinfunction "2_2") (pintype "input"))
      (node (ref "MPU6050") (pin "20") (pinfunction "CPOUT_20") (pintype "unspecified"))
    )
    (net (code "22") (name "Net-(MPU6050-REGOUT)") (class "Default")
      (node (ref "C8") (pin "2") (pinfunction "2_2") (pintype "unspecified"))
      (node (ref "MPU6050") (pin "10") (pinfunction "REGOUT_10") (pintype "unspecified"))
    )
    (net (code "23") (name "Net-(PW5300-EN)") (class "Default")
      (node (ref "C16") (pin "2") (pinfunction "2_2") (pintype "unspecified"))
      (node (ref "C17") (pin "2") (pinfunction "2_2") (pintype "unspecified"))
      (node (ref "L2") (pin "1") (pinfunction "1_1") (pintype "unspecified"))
      (node (ref "PW5300") (pin "4") (pinfunction "EN_4") (pintype "unspecified"))
      (node (ref "PW5300") (pin "5") (pinfunction "VIN_5") (pintype "unspecified"))
      (node (ref "SW1") (pin "1") (pinfunction "1_1") (pintype "unspecified"))
    )
    (net (code "24") (name "Net-(PW5300-FB)") (class "Default")
      (node (ref "PW5300") (pin "3") (pinfunction "FB_3") (pintype "unspecified"))
      (node (ref "R15") (pin "1") (pinfunction "1_1") (pintype "input"))
      (node (ref "R16") (pin "2") (pinfunction "2_2") (pintype "input"))
    )
    (net (code "25") (name "Net-(PW5300-OCP)") (class "Default")
      (node (ref "PW5300") (pin "6") (pinfunction "OCP_6") (pintype "unspecified"))
      (node (ref "R14") (pin "2") (pinfunction "2_2") (pintype "input"))
    )
    (net (code "26") (name "Net-(Q1-Pad1)") (class "Default")
      (node (ref "Q1") (pin "1") (pinfunction "1_1") (pintype "input"))
      (node (ref "R7") (pin "2") (pinfunction "2_2") (pintype "input"))
    )
    (net (code "27") (name "Net-(Q1-Pad3)") (class "Default")
      (node (ref "Q1") (pin "3") (pinfunction "3_3") (pintype "input"))
      (node (ref "R8") (pin "1") (pinfunction "1_1") (pintype "input"))
    )
    (net (code "28") (name "Net-(Q2-D)") (class "Default")
      (node (ref "BAT1") (pin "1") (pinfunction "1_1") (pintype "unspecified"))
      (node (ref "C15") (pin "2") (pinfunction "2_2") (pintype "unspecified"))
      (node (ref "Q2") (pin "3") (pinfunction "D_3") (pintype "unspecified"))
      (node (ref "TP4056") (pin "5") (pinfunction "BAT_5") (pintype "unspecified"))
    )
    (net (code "29") (name "Net-(RT6150-FB)") (class "Default")
      (node (ref "R17") (pin "1") (pinfunction "1_1") (pintype "input"))
      (node (ref "R18") (pin "2") (pinfunction "2_2") (pintype "input"))
      (node (ref "RT6150") (pin "10") (pinfunction "FB_10") (pintype "input"))
    )
    (net (code "30") (name "Net-(RT6150-LX1)") (class "Default")
      (node (ref "L3") (pin "1") (pinfunction "1_1") (pintype "unspecified"))
      (node (ref "RT6150") (pin "4") (pinfunction "LX1_4") (pintype "input"))
    )
    (net (code "31") (name "Net-(RT6150-LX2)") (class "Default")
      (node (ref "L3") (pin "2") (pinfunction "2_2") (pintype "unspecified"))
      (node (ref "RT6150") (pin "2") (pinfunction "LX2_2") (pintype "input"))
    )
    (net (code "32") (name "Net-(RT6150-VOUT)") (class "Default")
      (node (ref "C23") (pin "2") (pinfunction "2_2") (pintype "unspecified"))
      (node (ref "C24") (pin "2") (pinfunction "2_2") (pintype "unspecified"))
      (node (ref "R17") (pin "2") (pinfunction "2_2") (pintype "input"))
      (node (ref "RT6150") (pin "1") (pinfunction "VOUT_1") (pintype "input"))
      (node (ref "RT9013") (pin "1") (pinfunction "VIN_1") (pintype "unspecified"))
      (node (ref "RT9013") (pin "3") (pinfunction "EN_3") (pintype "unspecified"))
    )
    (net (code "33") (name "Net-(STM32F103CBT6-VDDA)") (class "Default")
      (node (ref "C2") (pin "2") (pinfunction "2_2") (pintype "unspecified"))
      (node (ref "L1") (pin "1") (pinfunction "1_1") (pintype "unspecified"))
      (node (ref "STM32F103CBT6") (pin "9") (pinfunction "VDDA_9") (pintype "unspecified"))
    )
    (net (code "34") (name "Net-(TP4056-CHRG#)") (class "Default")
      (node (ref "R11") (pin "1") (pinfunction "1_1") (pintype "input"))
      (node (ref "TP4056") (pin "7") (pinfunction "CHRG#_7") (pintype "unspecified"))
    )
    (net (code "35") (name "Net-(TP4056-PROG)") (class "Default")
      (node (ref "R12") (pin "2") (pinfunction "2_2") (pintype "input"))
      (node (ref "TP4056") (pin "2") (pinfunction "PROG_2") (pintype "unspecified"))
    )
    (net (code "36") (name "Net-(TP4056-STDBY#)") (class "Default")
      (node (ref "R10") (pin "1") (pinfunction "1_1") (pintype "input"))
      (node (ref "TP4056") (pin "6") (pinfunction "STDBY#_6") (pintype "unspecified"))
    )
    (net (code "37") (name "Net-(USB1-CC1)") (class "Default")
      (node (ref "R9") (pin "2") (pinfunction "2_2") (pintype "input"))
      (node (ref "USB1") (pin "10") (pinfunction "CC2_10") (pintype "unspecified"))
      (node (ref "USB1") (pin "4") (pinfunction "CC1_4") (pintype "unspecified"))
    )
    (net (code "38") (name "OSC_IN") (class "Default")
      (node (ref "C12") (pin "2") (pinfunction "2_2") (pintype "input"))
      (node (ref "STM32F103CBT6") (pin "5") (pinfunction "PD0-OSC_IN_5") (pintype "unspecified"))
      (node (ref "X1") (pin "1") (pinfunction "1_1") (pintype "input"))
    )
    (net (code "39") (name "OSC_OUT") (class "Default")
      (node (ref "C13") (pin "2") (pinfunction "2_2") (pintype "input"))
      (node (ref "STM32F103CBT6") (pin "6") (pinfunction "PD1-OSC_OUT_6") (pintype "unspecified"))
      (node (ref "X1") (pin "3") (pinfunction "3_3") (pintype "input"))
    )
    (net (code "40") (name "PA1_LED") (class "Default")
      (node (ref "R1") (pin "2") (pinfunction "2_2") (pintype "input"))
      (node (ref "STM32F103CBT6") (pin "11") (pinfunction "PA1_11") (pintype "unspecified"))
    )
    (net (code "41") (name "PB1") (class "Default")
      (node (ref "STM32F103CBT6") (pin "19") (pinfunction "PB1_19") (pintype "unspecified"))
      (node (ref "SW2") (pin "2") (pinfunction "2_2") (pintype "unspecified"))
    )
    (net (code "42") (name "SPI2_MISO") (class "Default")
      (node (ref "FLASH1") (pin "2") (pinfunction "DO/IO1_2") (pintype "unspecified"))
      (node (ref "STM32F103CBT6") (pin "27") (pinfunction "PB14_27") (pintype "unspecified"))
    )
    (net (code "43") (name "SPI2_MOSI") (class "Default")
      (node (ref "FLASH1") (pin "5") (pinfunction "DI/IO0_5") (pintype "unspecified"))
      (node (ref "STM32F103CBT6") (pin "28") (pinfunction "PB15_28") (pintype "unspecified"))
    )
    (net (code "44") (name "SPI2_SCK") (class "Default")
      (node (ref "FLASH1") (pin "6") (pinfunction "CLK_6") (pintype "unspecified"))
      (node (ref "STM32F103CBT6") (pin "26") (pinfunction "PB13_26") (pintype "unspecified"))
    )
    (net (code "45") (name "SYS_JTCK-SWCLK") (class "Default")
      (node (ref "STLink1") (pin "3") (pinfunction "3_3") (pintype "unspecified"))
      (node (ref "STM32F103CBT6") (pin "37") (pinfunction "PA14_37") (pintype "unspecified"))
    )
    (net (code "46") (name "SYS_JTMS-SWDIO") (class "Default")
      (node (ref "STLink1") (pin "4") (pinfunction "4_4") (pintype "unspecified"))
      (node (ref "STM32F103CBT6") (pin "34") (pinfunction "PA13_34") (pintype "unspecified"))
    )
    (net (code "47") (name "USART1_RX") (class "Default")
      (node (ref "HC051") (pin "4") (pinfunction "4_4") (pintype "unspecified"))
      (node (ref "STM32F103CBT6") (pin "31") (pinfunction "PA10_31") (pintype "unspecified"))
    )
    (net (code "48") (name "USART1_TX") (class "Default")
      (node (ref "HC051") (pin "5") (pinfunction "5_5") (pintype "unspecified"))
      (node (ref "STM32F103CBT6") (pin "30") (pinfunction "PA9_30") (pintype "unspecified"))
    )
    (net (code "49") (name "USART3_RX") (class "Default")
      (node (ref "HC052") (pin "4") (pinfunction "4_4") (pintype "unspecified"))
      (node (ref "STM32F103CBT6") (pin "22") (pinfunction "PB11_22") (pintype "unspecified"))
    )
    (net (code "50") (name "USART3_TX") (class "Default")
      (node (ref "HC052") (pin "5") (pinfunction "5_5") (pintype "unspecified"))
      (node (ref "STM32F103CBT6") (pin "21") (pinfunction "PB10_21") (pintype "unspecified"))
    )
    (net (code "51") (name "VBAT_E") (class "Default")
      (node (ref "C1") (pin "2") (pinfunction "2_2") (pintype "unspecified"))
      (node (ref "STM32F103CBT6") (pin "1") (pinfunction "VBAT_1") (pintype "unspecified"))
    )
    (net (code "52") (name "VCC_USB") (class "Default")
      (node (ref "C14") (pin "2") (pinfunction "2_2") (pintype "unspecified"))
      (node (ref "D1") (pin "1") (pinfunction "A_1") (pintype "unspecified"))
      (node (ref "LED3") (pin "2") (pinfunction "A_2") (pintype "input"))
      (node (ref "LED4") (pin "2") (pinfunction "A_2") (pintype "input"))
      (node (ref "Q2") (pin "1") (pinfunction "G_1") (pintype "unspecified"))
      (node (ref "R13") (pin "2") (pinfunction "2_2") (pintype "input"))
      (node (ref "TP4056") (pin "4") (pinfunction "VCC_4") (pintype "unspecified"))
      (node (ref "TP4056") (pin "8") (pinfunction "CE_8") (pintype "unspecified"))
      (node (ref "USB1") (pin "11") (pinfunction "VBUS_11") (pintype "unspecified"))
      (node (ref "USB1") (pin "2") (pinfunction "VBUS_2") (pintype "unspecified"))
    )
    (net (code "53") (name "W25Q16_CHIP_SELECT") (class "Default")
      (node (ref "FLASH1") (pin "1") (pinfunction "/CS_1") (pintype "unspecified"))
      (node (ref "STM32F103CBT6") (pin "25") (pinfunction "PB12_25") (pintype "unspecified"))
    )
    (net (code "54") (name "unconnected-(FLASH1-IO2-Pad3)") (class "Default")
      (node (ref "FLASH1") (pin "3") (pinfunction "IO2_3") (pintype "unspecified+no_connect"))
    )
    (net (code "55") (name "unconnected-(FLASH1-IO3-Pad7)") (class "Default")
      (node (ref "FLASH1") (pin "7") (pinfunction "IO3_7") (pintype "unspecified+no_connect"))
    )
    (net (code "56") (name "unconnected-(HC051-Pad1)") (class "Default")
      (node (ref "HC051") (pin "1") (pinfunction "1_1") (pintype "unspecified+no_connect"))
    )
    (net (code "57") (name "unconnected-(HC051-Pad6)") (class "Default")
      (node (ref "HC051") (pin "6") (pinfunction "6_6") (pintype "unspecified+no_connect"))
    )
    (net (code "58") (name "unconnected-(HC052-Pad1)") (class "Default")
      (node (ref "HC052") (pin "1") (pinfunction "1_1") (pintype "unspecified+no_connect"))
    )
    (net (code "59") (name "unconnected-(HC052-Pad6)") (class "Default")
      (node (ref "HC052") (pin "6") (pinfunction "6_6") (pintype "unspecified+no_connect"))
    )
    (net (code "60") (name "unconnected-(MPU6050-AUX_CL-Pad7)") (class "Default")
      (node (ref "MPU6050") (pin "7") (pinfunction "AUX_CL_7") (pintype "unspecified+no_connect"))
    )
    (net (code "61") (name "unconnected-(MPU6050-AUX_DA-Pad6)") (class "Default")
      (node (ref "MPU6050") (pin "6") (pinfunction "AUX_DA_6") (pintype "unspecified+no_connect"))
    )
    (net (code "62") (name "unconnected-(MPU6050-EP-Pad25)") (class "Default")
      (node (ref "MPU6050") (pin "25") (pinfunction "EP_25") (pintype "unspecified+no_connect"))
    )
    (net (code "63") (name "unconnected-(MPU6050-NC-Pad2)") (class "Default")
      (node (ref "MPU6050") (pin "2") (pinfunction "NC_2") (pintype "unspecified+no_connect"))
    )
    (net (code "64") (name "unconnected-(MPU6050-NC-Pad3)") (class "Default")
      (node (ref "MPU6050") (pin "3") (pinfunction "NC_3") (pintype "unspecified+no_connect"))
    )
    (net (code "65") (name "unconnected-(MPU6050-NC-Pad4)") (class "Default")
      (node (ref "MPU6050") (pin "4") (pinfunction "NC_4") (pintype "unspecified+no_connect"))
    )
    (net (code "66") (name "unconnected-(MPU6050-NC-Pad5)") (class "Default")
      (node (ref "MPU6050") (pin "5") (pinfunction "NC_5") (pintype "unspecified+no_connect"))
    )
    (net (code "67") (name "unconnected-(MPU6050-NC-Pad14)") (class "Default")
      (node (ref "MPU6050") (pin "14") (pinfunction "NC_14") (pintype "unspecified+no_connect"))
    )
    (net (code "68") (name "unconnected-(MPU6050-NC-Pad15)") (class "Default")
      (node (ref "MPU6050") (pin "15") (pinfunction "NC_15") (pintype "unspecified+no_connect"))
    )
    (net (code "69") (name "unconnected-(MPU6050-NC-Pad16)") (class "Default")
      (node (ref "MPU6050") (pin "16") (pinfunction "NC_16") (pintype "unspecified+no_connect"))
    )
    (net (code "70") (name "unconnected-(MPU6050-NC-Pad17)") (class "Default")
      (node (ref "MPU6050") (pin "17") (pinfunction "NC_17") (pintype "unspecified+no_connect"))
    )
    (net (code "71") (name "unconnected-(MPU6050-RESV-Pad19)") (class "Default")
      (node (ref "MPU6050") (pin "19") (pinfunction "RESV_19") (pintype "unspecified+no_connect"))
    )
    (net (code "72") (name "unconnected-(MPU6050-RESV-Pad21)") (class "Default")
      (node (ref "MPU6050") (pin "21") (pinfunction "RESV_21") (pintype "unspecified+no_connect"))
    )
    (net (code "73") (name "unconnected-(MPU6050-RESV-Pad22)") (class "Default")
      (node (ref "MPU6050") (pin "22") (pinfunction "RESV_22") (pintype "unspecified+no_connect"))
    )
    (net (code "74") (name "unconnected-(RT9013-NC-Pad4)") (class "Default")
      (node (ref "RT9013") (pin "4") (pinfunction "NC_4") (pintype "unspecified+no_connect"))
    )
    (net (code "75") (name "unconnected-(STM32F103CBT6-PA4-Pad14)") (class "Default")
      (node (ref "STM32F103CBT6") (pin "14") (pinfunction "PA4_14") (pintype "unspecified+no_connect"))
    )
    (net (code "76") (name "unconnected-(STM32F103CBT6-PA5-Pad15)") (class "Default")
      (node (ref "STM32F103CBT6") (pin "15") (pinfunction "PA5_15") (pintype "unspecified+no_connect"))
    )
    (net (code "77") (name "unconnected-(STM32F103CBT6-PA6-Pad16)") (class "Default")
      (node (ref "STM32F103CBT6") (pin "16") (pinfunction "PA6_16") (pintype "unspecified+no_connect"))
    )
    (net (code "78") (name "unconnected-(STM32F103CBT6-PA7-Pad17)") (class "Default")
      (node (ref "STM32F103CBT6") (pin "17") (pinfunction "PA7_17") (pintype "unspecified+no_connect"))
    )
    (net (code "79") (name "unconnected-(STM32F103CBT6-PA11-Pad32)") (class "Default")
      (node (ref "STM32F103CBT6") (pin "32") (pinfunction "PA11_32") (pintype "unspecified+no_connect"))
    )
    (net (code "80") (name "unconnected-(STM32F103CBT6-PA12-Pad33)") (class "Default")
      (node (ref "STM32F103CBT6") (pin "33") (pinfunction "PA12_33") (pintype "unspecified+no_connect"))
    )
    (net (code "81") (name "unconnected-(STM32F103CBT6-PA15-Pad38)") (class "Default")
      (node (ref "STM32F103CBT6") (pin "38") (pinfunction "PA15_38") (pintype "unspecified+no_connect"))
    )
    (net (code "82") (name "unconnected-(STM32F103CBT6-PB2-Pad20)") (class "Default")
      (node (ref "STM32F103CBT6") (pin "20") (pinfunction "PB2_20") (pintype "unspecified+no_connect"))
    )
    (net (code "83") (name "unconnected-(STM32F103CBT6-PB3-Pad39)") (class "Default")
      (node (ref "STM32F103CBT6") (pin "39") (pinfunction "PB3_39") (pintype "unspecified+no_connect"))
    )
    (net (code "84") (name "unconnected-(STM32F103CBT6-PB5-Pad41)") (class "Default")
      (node (ref "STM32F103CBT6") (pin "41") (pinfunction "PB5_41") (pintype "unspecified+no_connect"))
    )
    (net (code "85") (name "unconnected-(STM32F103CBT6-PB6-Pad42)") (class "Default")
      (node (ref "STM32F103CBT6") (pin "42") (pinfunction "PB6_42") (pintype "unspecified+no_connect"))
    )
    (net (code "86") (name "unconnected-(STM32F103CBT6-PB7-Pad43)") (class "Default")
      (node (ref "STM32F103CBT6") (pin "43") (pinfunction "PB7_43") (pintype "unspecified+no_connect"))
    )
    (net (code "87") (name "unconnected-(STM32F103CBT6-PC13-TAMPER-RTC-Pad2)") (class "Default")
      (node (ref "STM32F103CBT6") (pin "2") (pinfunction "PC13-TAMPER-RTC_2") (pintype "unspecified+no_connect"))
    )
    (net (code "88") (name "unconnected-(STM32F103CBT6-PC14-OSC32_IN-Pad3)") (class "Default")
      (node (ref "STM32F103CBT6") (pin "3") (pinfunction "PC14-OSC32_IN_3") (pintype "unspecified+no_connect"))
    )
    (net (code "89") (name "unconnected-(STM32F103CBT6-PC15-OSC32_OUT-Pad4)") (class "Default")
      (node (ref "STM32F103CBT6") (pin "4") (pinfunction "PC15-OSC32_OUT_4") (pintype "unspecified+no_connect"))
    )
    (net (code "90") (name "unconnected-(SW1-Pad3)") (class "Default")
      (node (ref "SW1") (pin "3") (pinfunction "3_3") (pintype "unspecified+no_connect"))
    )
    (net (code "91") (name "unconnected-(SW2-Pad3)") (class "Default")
      (node (ref "SW2") (pin "3") (pinfunction "3_3") (pintype "unspecified+no_connect"))
    )
    (net (code "92") (name "unconnected-(USB1-DN1-Pad7)") (class "Default")
      (node (ref "USB1") (pin "7") (pinfunction "DN1_7") (pintype "unspecified+no_connect"))
    )
    (net (code "93") (name "unconnected-(USB1-DN2-Pad5)") (class "Default")
      (node (ref "USB1") (pin "5") (pinfunction "DN2_5") (pintype "unspecified+no_connect"))
    )
    (net (code "94") (name "unconnected-(USB1-DP1-Pad6)") (class "Default")
      (node (ref "USB1") (pin "6") (pinfunction "DP1_6") (pintype "unspecified+no_connect"))
    )
    (net (code "95") (name "unconnected-(USB1-DP2-Pad8)") (class "Default")
      (node (ref "USB1") (pin "8") (pinfunction "DP2_8") (pintype "unspecified+no_connect"))
    )
    (net (code "96") (name "unconnected-(USB1-SBU1-Pad9)") (class "Default")
      (node (ref "USB1") (pin "9") (pinfunction "SBU1_9") (pintype "unspecified+no_connect"))
    )
    (net (code "97") (name "unconnected-(USB1-SBU2-Pad3)") (class "Default")
      (node (ref "USB1") (pin "3") (pinfunction "SBU2_3") (pintype "unspecified+no_connect"))
    )
  )
)
